# AD5450.net
KiCad netlist of a schematic drawn in Altium Designer
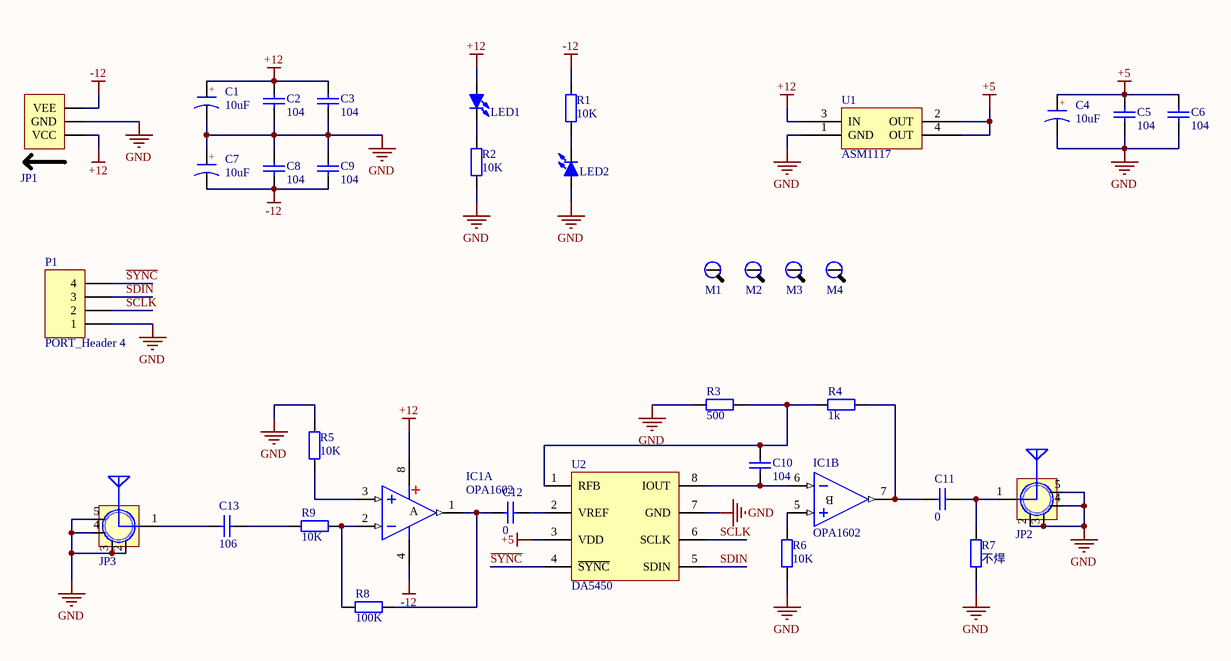
[diagram p0: AD5450.SchDoc]

(export (version "E")
  (design (tool "Eeschema 10.0.6"))
  (components
    (comp (ref "C1")
      (value "10uF")
      (footprint "CASE-A_3216")
      (description "贴片钽电容")
      (fields (field (name "Comment") "CAP+"))
      (libsource (lib "Cooperation") (part "0CAP+"))
    )
    (comp (ref "C2") (value "104") (footprint "C0603") (libsource (lib "Cooperation") (part "CAP_104")))
    (comp (ref "C3") (value "104") (footprint "C0603") (libsource (lib "Cooperation") (part "CAP_104")))
    (comp (ref "C4")
      (value "10uF")
      (footprint "CASE-A_3216")
      (description "贴片钽电容")
      (fields (field (name "Comment") "CAP+"))
      (libsource (lib "Cooperation") (part "0CAP+"))
    )
    (comp (ref "C5") (value "104") (footprint "C0603") (libsource (lib "Cooperation") (part "CAP_104")))
    (comp (ref "C6") (value "104") (footprint "C0603") (libsource (lib "Cooperation") (part "CAP_104")))
    (comp (ref "C7")
      (value "10uF")
      (footprint "CASE-A_3216")
      (description "贴片钽电容")
      (fields (field (name "Comment") "CAP+"))
      (libsource (lib "Cooperation") (part "0CAP+"))
    )
    (comp (ref "C8") (value "104") (footprint "C0603") (libsource (lib "Cooperation") (part "CAP_104")))
    (comp (ref "C9") (value "104") (footprint "C0603") (libsource (lib "Cooperation") (part "CAP_104")))
    (comp (ref "C10") (value "104") (footprint "C0603") (libsource (lib "Cooperation") (part "CAP_104")))
    (comp (ref "C11")
      (value "0")
      (footprint "C0603")
      (fields (field (name "Comment") "104"))
      (libsource (lib "Cooperation") (part "CAP_104"))
    )
    (comp (ref "C12")
      (value "0")
      (footprint "C0603")
      (fields (field (name "Comment") "104"))
      (libsource (lib "Cooperation") (part "CAP_104"))
    )
    (comp (ref "C13")
      (value "106")
      (footprint "C0603")
      (fields (field (name "Comment") "104"))
      (libsource (lib "Cooperation") (part "CAP_104"))
    )
    (comp (ref "IC1")
      (value "OPA1602")
      (footprint "SOP8_N")
      (description "双路运放")
      (fields (field (name "版权归属") "源创客"))
      (libsource (lib "1.1 - 常见芯片") (part "LM358"))
    )
    (comp (ref "JP1")
      (value "HDR-1X3")
      (footprint "Power_IN_3.81-3P")
      (description "3P接插件,模块双电源供电口")
      (fields (field (name "版权归属") "源创客"))
      (libsource (lib "Cooperation") (part "PORT_Power_IN3"))
    )
    (comp (ref "JP2")
      (value "SMA WIFI 天线接口")
      (footprint "SMA")
      (description "SMA-2.4G射频天线接口")
      (fields (field (name "版权归属") "源创客"))
      (libsource (lib "") (part "PORT_SMA_1"))
    )
    (comp (ref "JP3")
      (value "SMA WIFI 天线接口")
      (footprint "SMA")
      (description "SMA-2.4G射频天线接口")
      (fields (field (name "版权归属") "源创客"))
      (libsource (lib "Cooperation") (part "PORT_SMA"))
    )
    (comp (ref "LED1")
      (value "红色")
      (footprint "LED 0603")
      (description "贴片LED")
      (libsource (lib "Cooperation") (part "ELSE_LED_SMD"))
    )
    (comp (ref "LED2")
      (value "红色")
      (footprint "LED 0603")
      (description "贴片LED")
      (libsource (lib "Cooperation") (part "ELSE_LED_SMD"))
    )
    (comp (ref "M1")
      (value "M3")
      (footprint "M3x10_L")
      (description "螺丝")
      (libsource (lib "Cooperation") (part "ELSE_M3_screw"))
    )
    (comp (ref "M2")
      (value "M3")
      (footprint "M3x10_L")
      (description "螺丝")
      (libsource (lib "Cooperation") (part "ELSE_M3_screw"))
    )
    (comp (ref "M3")
      (value "M3")
      (footprint "M3x10_L")
      (description "螺丝")
      (libsource (lib "Cooperation") (part "ELSE_M3_screw"))
    )
    (comp (ref "M4")
      (value "M3")
      (footprint "M3x10_L")
      (description "螺丝")
      (libsource (lib "Cooperation") (part "ELSE_M3_screw"))
    )
    (comp (ref "P1")
      (value "PORT_Header 4")
      (footprint "HDR1X4")
      (description "Header, 4-Pin")
      (fields (field (name "PUBLISHER") "Altium Limited"))
      (libsource (lib "Cooperation") (part "PORT_Header 4"))
    )
    (comp (ref "R1")
      (value "10K")
      (footprint "R-0805")
      (description "小功率贴片电组")
      (fields (field (name "Comment") "Res"))
      (libsource (lib "") (part "0RES_1"))
    )
    (comp (ref "R2")
      (value "10K")
      (footprint "R-0805")
      (description "小功率贴片电组")
      (fields (field (name "Comment") "Res"))
      (libsource (lib "Cooperation") (part "0RES"))
    )
    (comp (ref "R3")
      (value "500")
      (footprint "R-0805")
      (description "小功率贴片电组")
      (fields (field (name "Comment") "Res"))
      (libsource (lib "") (part "0RES_2"))
    )
    (comp (ref "R4")
      (value "1k")
      (footprint "R-0805")
      (description "小功率贴片电组")
      (fields (field (name "Comment") "Res"))
      (libsource (lib "") (part "0RES_2"))
    )
    (comp (ref "R5")
      (value "10K")
      (footprint "R-0805")
      (description "小功率贴片电组")
      (fields (field (name "Comment") "Res"))
      (libsource (lib "Cooperation") (part "0RES"))
    )
    (comp (ref "R6")
      (value "10K")
      (footprint "R-0805")
      (description "小功率贴片电组")
      (fields (field (name "Comment") "Res"))
      (libsource (lib "Cooperation") (part "0RES"))
    )
    (comp (ref "R7")
      (value "不焊")
      (footprint "R-0805")
      (description "小功率贴片电组")
      (fields (field (name "Comment") "Res"))
      (libsource (lib "Cooperation") (part "0RES"))
    )
    (comp (ref "R8")
      (value "100K")
      (footprint "R-0805")
      (description "小功率贴片电组")
      (fields (field (name "Comment") "Res"))
      (libsource (lib "") (part "0RES_2"))
    )
    (comp (ref "R9")
      (value "10K")
      (footprint "R-0805")
      (description "小功率贴片电组")
      (fields (field (name "Comment") "Res"))
      (libsource (lib "") (part "0RES_3"))
    )
    (comp (ref "U1")
      (value "ASM1117")
      (footprint "SOT-223")
      (description "3.3V稳压芯片")
      (libsource (lib "主集成库") (part "ASM1117"))
    )
    (comp (ref "U2") (value "DA5450") (footprint "SOT23-8L") (libsource (lib "Cooperation") (part "DA5450")))
  )
  (nets
    (net (code "1") (name "+5") (class "Default")
      (node (ref "C4") (pin "1") (pinfunction "A_1") (pintype "passive"))
      (node (ref "C5") (pin "2") (pinfunction "2_2") (pintype "passive"))
      (node (ref "C6") (pin "2") (pinfunction "2_2") (pintype "passive"))
      (node (ref "U1") (pin "2") (pinfunction "OUT_2") (pintype "passive"))
      (node (ref "U1") (pin "4") (pinfunction "OUT_4") (pintype "passive"))
      (node (ref "U2") (pin "3") (pinfunction "VDD_3") (pintype "passive"))
    )
    (net (code "2") (name "+12") (class "Default")
      (node (ref "C1") (pin "1") (pinfunction "A_1") (pintype "passive"))
      (node (ref "C2") (pin "2") (pinfunction "2_2") (pintype "passive"))
      (node (ref "C3") (pin "2") (pinfunction "2_2") (pintype "passive"))
      (node (ref "IC1") (pin "8") (pinfunction "V+_8") (pintype "power_in"))
      (node (ref "JP1") (pin "1") (pinfunction "VCC_1") (pintype "passive"))
      (node (ref "LED1") (pin "1") (pinfunction "A_1") (pintype "passive"))
      (node (ref "U1") (pin "3") (pinfunction "IN_3") (pintype "passive"))
    )
    (net (code "3") (name "-12") (class "Default")
      (node (ref "C7") (pin "2") (pinfunction "K_2") (pintype "passive"))
      (node (ref "C8") (pin "1") (pinfunction "1_1") (pintype "passive"))
      (node (ref "C9") (pin "1") (pinfunction "1_1") (pintype "passive"))
      (node (ref "IC1") (pin "4") (pinfunction "V-_4") (pintype "power_in"))
      (node (ref "JP1") (pin "3") (pinfunction "VEE_3") (pintype "passive"))
      (node (ref "R1") (pin "1") (pinfunction "1_1") (pintype "passive"))
    )
    (net (code "4") (name "/SCLK") (class "Default")
      (node (ref "P1") (pin "2") (pinfunction "2_2") (pintype "passive"))
      (node (ref "U2") (pin "6") (pinfunction "SCLK_6") (pintype "passive"))
    )
    (net (code "5") (name "/SDIN") (class "Default")
      (node (ref "P1") (pin "3") (pinfunction "3_3") (pintype "passive"))
      (node (ref "U2") (pin "5") (pinfunction "SDIN_5") (pintype "passive"))
    )
    (net (code "6") (name "/~{SYNC}") (class "Default")
      (node (ref "P1") (pin "4") (pinfunction "4_4") (pintype "passive"))
      (node (ref "U2") (pin "4") (pinfunction "~{SYNC}_4") (pintype "passive"))
    )
    (net (code "7") (name "GND") (class "Default")
      (node (ref "C1") (pin "2") (pinfunction "K_2") (pintype "passive"))
      (node (ref "C2") (pin "1") (pinfunction "1_1") (pintype "passive"))
      (node (ref "C3") (pin "1") (pinfunction "1_1") (pintype "passive"))
      (node (ref "C4") (pin "2") (pinfunction "K_2") (pintype "passive"))
      (node (ref "C5") (pin "1") (pinfunction "1_1") (pintype "passive"))
      (node (ref "C6") (pin "1") (pinfunction "1_1") (pintype "passive"))
      (node (ref "C7") (pin "1") (pinfunction "A_1") (pintype "passive"))
      (node (ref "C8") (pin "2") (pinfunction "2_2") (pintype "passive"))
      (node (ref "C9") (pin "2") (pinfunction "2_2") (pintype "passive"))
      (node (ref "JP1") (pin "2") (pinfunction "GND_2") (pintype "passive"))
      (node (ref "JP2") (pin "2") (pinfunction "GND_2") (pintype "passive"))
      (node (ref "JP2") (pin "3") (pinfunction "GND_3") (pintype "passive"))
      (node (ref "JP2") (pin "4") (pinfunction "GND_4") (pintype "passive"))
      (node (ref "JP2") (pin "5") (pinfunction "GND_5") (pintype "passive"))
      (node (ref "JP3") (pin "2") (pinfunction "GND_2") (pintype "passive"))
      (node (ref "JP3") (pin "3") (pinfunction "GND_3") (pintype "passive"))
      (node (ref "JP3") (pin "4") (pinfunction "GND_4") (pintype "passive"))
      (node (ref "JP3") (pin "5") (pinfunction "GND_5") (pintype "passive"))
      (node (ref "LED2") (pin "1") (pinfunction "A_1") (pintype "passive"))
      (node (ref "P1") (pin "1") (pinfunction "1_1") (pintype "passive"))
      (node (ref "R2") (pin "1") (pinfunction "1_1") (pintype "passive"))
      (node (ref "R3") (pin "1") (pinfunction "1_1") (pintype "passive"))
      (node (ref "R5") (pin "2") (pinfunction "2_2") (pintype "passive"))
      (node (ref "R6") (pin "1") (pinfunction "1_1") (pintype "passive"))
      (node (ref "R7") (pin "1") (pinfunction "1_1") (pintype "passive"))
      (node (ref "U1") (pin "1") (pinfunction "GND_1") (pintype "passive"))
      (node (ref "U2") (pin "7") (pinfunction "GND_7") (pintype "passive"))
    )
    (net (code "8") (name "Net-(C13-Pad2)") (class "Default")
      (node (ref "C13") (pin "2") (pinfunction "2_2") (pintype "passive"))
      (node (ref "R9") (pin "2") (pinfunction "2_2") (pintype "passive"))
    )
    (net (code "9") (name "Net-(IC1A-IN+)") (class "Default")
      (node (ref "IC1") (pin "3") (pinfunction "IN+_3") (pintype "input"))
      (node (ref "R5") (pin "1") (pinfunction "1_1") (pintype "passive"))
    )
    (net (code "10") (name "Net-(IC1A-IN-)") (class "Default")
      (node (ref "IC1") (pin "2") (pinfunction "IN-_2") (pintype "input"))
      (node (ref "R8") (pin "1") (pinfunction "1_1") (pintype "passive"))
      (node (ref "R9") (pin "1") (pinfunction "1_1") (pintype "passive"))
    )
    (net (code "11") (name "Net-(IC1A-OUT)") (class "Default")
      (node (ref "C12") (pin "1") (pinfunction "1_1") (pintype "passive"))
      (node (ref "IC1") (pin "1") (pinfunction "OUT_1") (pintype "output"))
      (node (ref "R8") (pin "2") (pinfunction "2_2") (pintype "passive"))
    )
    (net (code "12") (name "Net-(IC1B-IN+)") (class "Default")
      (node (ref "IC1") (pin "5") (pinfunction "IN+_5") (pintype "input"))
      (node (ref "R6") (pin "2") (pinfunction "2_2") (pintype "passive"))
    )
    (net (code "13") (name "Net-(IC1B-IN-)") (class "Default")
      (node (ref "C10") (pin "1") (pinfunction "1_1") (pintype "passive"))
      (node (ref "IC1") (pin "6") (pinfunction "IN-_6") (pintype "input"))
      (node (ref "U2") (pin "8") (pinfunction "IOUT_8") (pintype "passive"))
    )
    (net (code "14") (name "Net-(IC1B-OUT)") (class "Default")
      (node (ref "C11") (pin "2") (pinfunction "2_2") (pintype "passive"))
      (node (ref "IC1") (pin "7") (pinfunction "OUT_7") (pintype "output"))
      (node (ref "R4") (pin "2") (pinfunction "2_2") (pintype "passive"))
    )
    (net (code "15") (name "Net-(JP2-SINGLE)") (class "Default")
      (node (ref "C11") (pin "1") (pinfunction "1_1") (pintype "passive"))
      (node (ref "JP2") (pin "1") (pinfunction "SINGLE_1") (pintype "passive"))
      (node (ref "R7") (pin "2") (pinfunction "2_2") (pintype "passive"))
    )
    (net (code "16") (name "Net-(JP3-SINGLE)") (class "Default")
      (node (ref "C13") (pin "1") (pinfunction "1_1") (pintype "passive"))
      (node (ref "JP3") (pin "1") (pinfunction "SINGLE_1") (pintype "passive"))
    )
    (net (code "17") (name "Net-(LED1-K)") (class "Default")
      (node (ref "LED1") (pin "2") (pinfunction "K_2") (pintype "passive"))
      (node (ref "R2") (pin "2") (pinfunction "2_2") (pintype "passive"))
    )
    (net (code "18") (name "Net-(LED2-K)") (class "Default")
      (node (ref "LED2") (pin "2") (pinfunction "K_2") (pintype "passive"))
      (node (ref "R1") (pin "2") (pinfunction "2_2") (pintype "passive"))
    )
    (net (code "19") (name "Net-(U2-RFB)") (class "Default")
      (node (ref "C10") (pin "2") (pinfunction "2_2") (pintype "passive"))
      (node (ref "R3") (pin "2") (pinfunction "2_2") (pintype "passive"))
      (node (ref "R4") (pin "1") (pinfunction "1_1") (pintype "passive"))
      (node (ref "U2") (pin "1") (pinfunction "RFB_1") (pintype "passive"))
    )
    (net (code "20") (name "Net-(U2-VREF)") (class "Default")
      (node (ref "C12") (pin "2") (pinfunction "2_2") (pintype "passive"))
      (node (ref "U2") (pin "2") (pinfunction "VREF_2") (pintype "passive"))
    )
    (net (code "21") (name "unconnected-(M1-Pad1)") (class "Default")
      (node (ref "M1") (pin "1") (pinfunction "1_1") (pintype "passive"))
    )
    (net (code "22") (name "unconnected-(M2-Pad1)") (class "Default")
      (node (ref "M2") (pin "1") (pinfunction "1_1") (pintype "passive"))
    )
    (net (code "23") (name "unconnected-(M3-Pad1)") (class "Default")
      (node (ref "M3") (pin "1") (pinfunction "1_1") (pintype "passive"))
    )
    (net (code "24") (name "unconnected-(M4-Pad1)") (class "Default")
      (node (ref "M4") (pin "1") (pinfunction "1_1") (pintype "passive"))
    )
  )
)
